# usb_board.net
KiCad netlist of a schematic drawn in Altium Designer
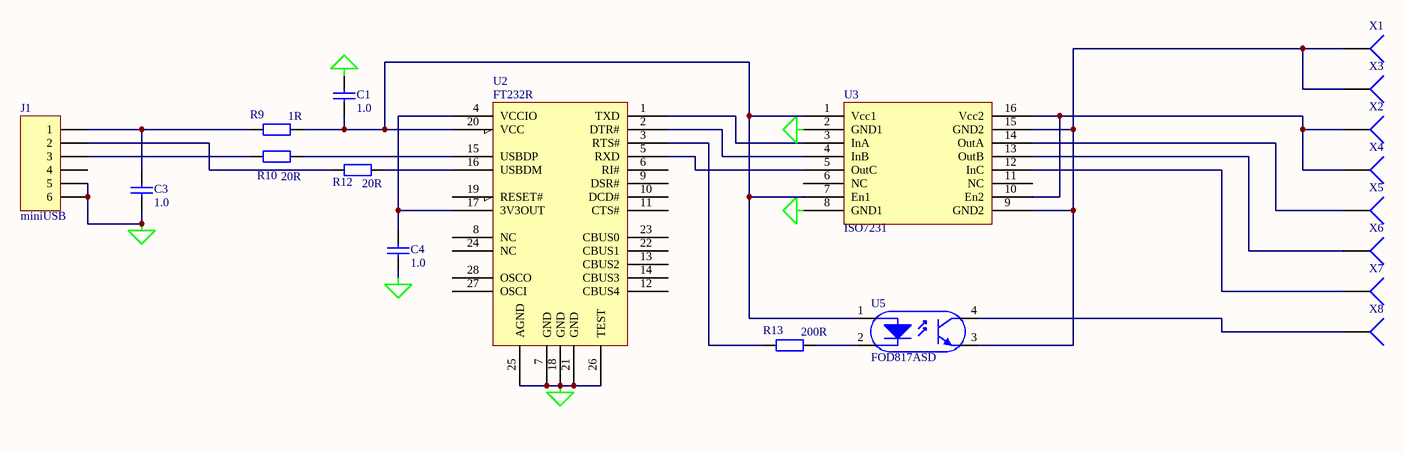
[diagram p0: usb_board.SchDoc]

(export (version "E")
  (design (tool "Eeschema 10.0.6"))
  (components
    (comp (ref "C1")
      (value "1.0")
      (footprint "_1206")
      (description "Capacitor (Semiconductor SIM Model)")
      (fields (field (name "MANUFACTURER") "Generic Components") (field (name "PUBLISHER") "Altium Limited"))
      (libsource (lib "Miscellaneous Devices") (part "Cap Semi"))
    )
    (comp (ref "C3")
      (value "1.0")
      (footprint "C3216-1206")
      (description "Capacitor (Semiconductor SIM Model)")
      (fields (field (name "MANUFACTURER") "Generic Components") (field (name "PUBLISHER") "Altium Limited"))
      (libsource (lib "Miscellaneous Devices") (part "Cap Semi"))
    )
    (comp (ref "C4")
      (value "1.0")
      (footprint "C3216-1206")
      (description "Capacitor (Semiconductor SIM Model)")
      (fields (field (name "MANUFACTURER") "Generic Components") (field (name "PUBLISHER") "Altium Limited"))
      (libsource (lib "Miscellaneous Devices") (part "Cap Semi"))
    )
    (comp (ref "J1")
      (value "miniUSB")
      (footprint "USBmini")
      (description "Header, 6-Pin")
      (fields (field (name "PUBLISHER") "Altium Limited"))
      (libsource (lib "Miscellaneous Connectors") (part "Header 6"))
    )
    (comp (ref "R9") (value "1R") (footprint "_1206") (libsource (lib "igorenja") (part "RES")))
    (comp (ref "R10") (value "20R") (footprint "_1206") (libsource (lib "igorenja") (part "RES")))
    (comp (ref "R12") (value "20R") (footprint "_1206") (libsource (lib "igorenja") (part "RES")))
    (comp (ref "R13") (value "200R") (footprint "_1206") (libsource (lib "igorenja") (part "RES")))
    (comp (ref "U2")
      (value "FT232R")
      (footprint "SOP65P780-28L")
      (libsource (lib "igorenja") (part "FT232R"))
    )
    (comp (ref "U3") (value "ISO7231") (libsource (lib "PAL") (part "ISO7231")))
    (comp (ref "U5") (value "FOD817ASD") (footprint "FOD817ASD") (libsource (lib "PAL") (part "F00817ASD")))
    (comp (ref "X1")
      (value "~")
      (footprint "PIN1")
      (description "Socket")
      (fields (field (name "MANUFACTURER") "Generic Components") (field (name "PUBLISHER") "Altium Limited"))
      (libsource (lib "Miscellaneous Connectors") (part "Socket"))
    )
    (comp (ref "X2")
      (value "~")
      (footprint "PIN1")
      (description "Socket")
      (fields (field (name "MANUFACTURER") "Generic Components") (field (name "PUBLISHER") "Altium Limited"))
      (libsource (lib "Miscellaneous Connectors") (part "Socket"))
    )
    (comp (ref "X3")
      (value "~")
      (footprint "PIN1")
      (description "Socket")
      (fields (field (name "MANUFACTURER") "Generic Components") (field (name "PUBLISHER") "Altium Limited"))
      (libsource (lib "Miscellaneous Connectors") (part "Socket"))
    )
    (comp (ref "X4")
      (value "~")
      (footprint "PIN1")
      (description "Socket")
      (fields (field (name "MANUFACTURER") "Generic Components") (field (name "PUBLISHER") "Altium Limited"))
      (libsource (lib "Miscellaneous Connectors") (part "Socket"))
    )
    (comp (ref "X5")
      (value "~")
      (footprint "PIN1")
      (description "Socket")
      (fields (field (name "MANUFACTURER") "Generic Components") (field (name "PUBLISHER") "Altium Limited"))
      (libsource (lib "Miscellaneous Connectors") (part "Socket"))
    )
    (comp (ref "X6")
      (value "~")
      (footprint "PIN1")
      (description "Socket")
      (fields (field (name "MANUFACTURER") "Generic Components") (field (name "PUBLISHER") "Altium Limited"))
      (libsource (lib "Miscellaneous Connectors") (part "Socket"))
    )
    (comp (ref "X7")
      (value "~")
      (footprint "PIN1")
      (description "Socket")
      (fields (field (name "MANUFACTURER") "Generic Components") (field (name "PUBLISHER") "Altium Limited"))
      (libsource (lib "Miscellaneous Connectors") (part "Socket"))
    )
    (comp (ref "X8")
      (value "~")
      (footprint "PIN1")
      (description "Socket")
      (fields (field (name "MANUFACTURER") "Generic Components") (field (name "PUBLISHER") "Altium Limited"))
      (libsource (lib "Miscellaneous Connectors") (part "Socket"))
    )
  )
  (nets
    (net (code "1") (name "GND_USB") (class "Default")
      (node (ref "C1") (pin "1") (pinfunction "1_1") (pintype "passive"))
      (node (ref "C3") (pin "1") (pinfunction "1_1") (pintype "passive"))
      (node (ref "C4") (pin "1") (pinfunction "1_1") (pintype "passive"))
      (node (ref "J1") (pin "5") (pinfunction "5_5") (pintype "passive"))
      (node (ref "J1") (pin "6") (pinfunction "6_6") (pintype "passive"))
      (node (ref "U2") (pin "18") (pinfunction "GND_18") (pintype "passive"))
      (node (ref "U2") (pin "21") (pinfunction "GND_21") (pintype "passive"))
      (node (ref "U2") (pin "25") (pinfunction "AGND_25") (pintype "passive"))
      (node (ref "U2") (pin "26") (pinfunction "TEST_26") (pintype "passive"))
      (node (ref "U2") (pin "7") (pinfunction "GND_7") (pintype "passive"))
      (node (ref "U3") (pin "2") (pinfunction "GND1_2") (pintype "passive"))
      (node (ref "U3") (pin "8") (pinfunction "GND1_8") (pintype "passive"))
    )
    (net (code "2") (name "Net-(C3-Pad2)") (class "Default")
      (node (ref "C3") (pin "2") (pinfunction "2_2") (pintype "passive"))
      (node (ref "J1") (pin "1") (pinfunction "1_1") (pintype "passive"))
      (node (ref "R9") (pin "1") (pinfunction "1_1") (pintype "passive"))
    )
    (net (code "3") (name "Net-(J1-Pad2)") (class "Default")
      (node (ref "J1") (pin "2") (pinfunction "2_2") (pintype "passive"))
      (node (ref "R12") (pin "1") (pinfunction "1_1") (pintype "passive"))
    )
    (net (code "4") (name "Net-(J1-Pad3)") (class "Default")
      (node (ref "J1") (pin "3") (pinfunction "3_3") (pintype "passive"))
      (node (ref "R10") (pin "1") (pinfunction "1_1") (pintype "passive"))
    )
    (net (code "5") (name "Net-(U2-3V3OUT)") (class "Default")
      (node (ref "C4") (pin "2") (pinfunction "2_2") (pintype "passive"))
      (node (ref "U2") (pin "17") (pinfunction "3V3OUT_17") (pintype "passive"))
      (node (ref "U2") (pin "4") (pinfunction "VCCIO_4") (pintype "passive"))
    )
    (net (code "6") (name "Net-(U2-DTR#)") (class "Default")
      (node (ref "U2") (pin "2") (pinfunction "DTR#_2") (pintype "passive"))
      (node (ref "U3") (pin "4") (pinfunction "InB_4") (pintype "passive"))
    )
    (net (code "7") (name "Net-(U2-RTS#)") (class "Default")
      (node (ref "R13") (pin "1") (pinfunction "1_1") (pintype "passive"))
      (node (ref "U2") (pin "3") (pinfunction "RTS#_3") (pintype "passive"))
    )
    (net (code "8") (name "Net-(U2-RXD)") (class "Default")
      (node (ref "U2") (pin "5") (pinfunction "RXD_5") (pintype "passive"))
      (node (ref "U3") (pin "5") (pinfunction "OutC_5") (pintype "passive"))
    )
    (net (code "9") (name "Net-(U2-TXD)") (class "Default")
      (node (ref "U2") (pin "1") (pinfunction "TXD_1") (pintype "passive"))
      (node (ref "U3") (pin "3") (pinfunction "InA_3") (pintype "passive"))
    )
    (net (code "10") (name "Net-(U2-USBDM)") (class "Default")
      (node (ref "R12") (pin "2") (pinfunction "2_2") (pintype "passive"))
      (node (ref "U2") (pin "16") (pinfunction "USBDM_16") (pintype "passive"))
    )
    (net (code "11") (name "Net-(U2-USBDP)") (class "Default")
      (node (ref "R10") (pin "2") (pinfunction "2_2") (pintype "passive"))
      (node (ref "U2") (pin "15") (pinfunction "USBDP_15") (pintype "passive"))
    )
    (net (code "12") (name "Net-(U2-VCC)") (class "Default")
      (node (ref "C1") (pin "2") (pinfunction "2_2") (pintype "passive"))
      (node (ref "R9") (pin "2") (pinfunction "2_2") (pintype "passive"))
      (node (ref "U2") (pin "20") (pinfunction "VCC_20") (pintype "passive"))
      (node (ref "U3") (pin "1") (pinfunction "Vcc1_1") (pintype "passive"))
      (node (ref "U3") (pin "7") (pinfunction "En1_7") (pintype "passive"))
      (node (ref "U5") (pin "1") (pinfunction "0_1") (pintype "passive"))
    )
    (net (code "13") (name "Net-(U3-En2)") (class "Default")
      (node (ref "U3") (pin "10") (pinfunction "En2_10") (pintype "passive"))
      (node (ref "U3") (pin "16") (pinfunction "Vcc2_16") (pintype "passive"))
      (node (ref "X2") (pin "1") (pinfunction "1_1") (pintype "passive"))
      (node (ref "X4") (pin "1") (pinfunction "1_1") (pintype "passive"))
    )
    (net (code "14") (name "Net-(U3-InC)") (class "Default")
      (node (ref "U3") (pin "12") (pinfunction "InC_12") (pintype "passive"))
      (node (ref "X7") (pin "1") (pinfunction "1_1") (pintype "passive"))
    )
    (net (code "15") (name "Net-(U3-OutA)") (class "Default")
      (node (ref "U3") (pin "14") (pinfunction "OutA_14") (pintype "passive"))
      (node (ref "X5") (pin "1") (pinfunction "1_1") (pintype "passive"))
    )
    (net (code "16") (name "Net-(U3-OutB)") (class "Default")
      (node (ref "U3") (pin "13") (pinfunction "OutB_13") (pintype "passive"))
      (node (ref "X6") (pin "1") (pinfunction "1_1") (pintype "passive"))
    )
    (net (code "17") (name "Net-(U5-1)") (class "Default")
      (node (ref "R13") (pin "2") (pinfunction "2_2") (pintype "passive"))
      (node (ref "U5") (pin "2") (pinfunction "1_2") (pintype "passive"))
    )
    (net (code "18") (name "Net-(U5-2)") (class "Default")
      (node (ref "U5") (pin "4") (pinfunction "2_4") (pintype "passive"))
      (node (ref "X8") (pin "1") (pinfunction "1_1") (pintype "passive"))
    )
    (net (code "19") (name "Net-(U5-4)") (class "Default")
      (node (ref "U3") (pin "15") (pinfunction "GND2_15") (pintype "passive"))
      (node (ref "U3") (pin "9") (pinfunction "GND2_9") (pintype "passive"))
      (node (ref "U5") (pin "3") (pinfunction "4_3") (pintype "passive"))
      (node (ref "X1") (pin "1") (pinfunction "1_1") (pintype "passive"))
      (node (ref "X3") (pin "1") (pinfunction "1_1") (pintype "passive"))
    )
    (net (code "20") (name "unconnected-(J1-Pad4)") (class "Default")
      (node (ref "J1") (pin "4") (pinfunction "4_4") (pintype "passive"))
    )
    (net (code "21") (name "unconnected-(U2-CBUS0-Pad23)") (class "Default")
      (node (ref "U2") (pin "23") (pinfunction "CBUS0_23") (pintype "passive"))
    )
    (net (code "22") (name "unconnected-(U2-CBUS1-Pad22)") (class "Default")
      (node (ref "U2") (pin "22") (pinfunction "CBUS1_22") (pintype "passive"))
    )
    (net (code "23") (name "unconnected-(U2-CBUS2-Pad13)") (class "Default")
      (node (ref "U2") (pin "13") (pinfunction "CBUS2_13") (pintype "passive"))
    )
    (net (code "24") (name "unconnected-(U2-CBUS3-Pad14)") (class "Default")
      (node (ref "U2") (pin "14") (pinfunction "CBUS3_14") (pintype "passive"))
    )
    (net (code "25") (name "unconnected-(U2-CBUS4-Pad12)") (class "Default")
      (node (ref "U2") (pin "12") (pinfunction "CBUS4_12") (pintype "passive"))
    )
    (net (code "26") (name "unconnected-(U2-CTS#-Pad11)") (class "Default")
      (node (ref "U2") (pin "11") (pinfunction "CTS#_11") (pintype "passive"))
    )
    (net (code "27") (name "unconnected-(U2-DCD#-Pad10)") (class "Default")
      (node (ref "U2") (pin "10") (pinfunction "DCD#_10") (pintype "passive"))
    )
    (net (code "28") (name "unconnected-(U2-DSR#-Pad9)") (class "Default")
      (node (ref "U2") (pin "9") (pinfunction "DSR#_9") (pintype "passive"))
    )
    (net (code "29") (name "unconnected-(U2-NC-Pad8)") (class "Default")
      (node (ref "U2") (pin "8") (pinfunction "NC_8") (pintype "passive"))
    )
    (net (code "30") (name "unconnected-(U2-NC-Pad24)") (class "Default")
      (node (ref "U2") (pin "24") (pinfunction "NC_24") (pintype "passive"))
    )
    (net (code "31") (name "unconnected-(U2-OSCI-Pad27)") (class "Default")
      (node (ref "U2") (pin "27") (pinfunction "OSCI_27") (pintype "passive"))
    )
    (net (code "32") (name "unconnected-(U2-OSCO-Pad28)") (class "Default")
      (node (ref "U2") (pin "28") (pinfunction "OSCO_28") (pintype "passive"))
    )
    (net (code "33") (name "unconnected-(U2-RESET#-Pad19)") (class "Default")
      (node (ref "U2") (pin "19") (pinfunction "RESET#_19") (pintype "passive"))
    )
    (net (code "34") (name "unconnected-(U2-RI#-Pad6)") (class "Default")
      (node (ref "U2") (pin "6") (pinfunction "RI#_6") (pintype "passive"))
    )
    (net (code "35") (name "unconnected-(U3-NC-Pad6)") (class "Default")
      (node (ref "U3") (pin "6") (pinfunction "NC_6") (pintype "passive"))
    )
    (net (code "36") (name "unconnected-(U3-NC-Pad11)") (class "Default")
      (node (ref "U3") (pin "11") (pinfunction "NC_11") (pintype "passive"))
    )
  )
)
